# loadSwitchBreakoutBoard.net
KiCad netlist of a schematic drawn in EAGLE
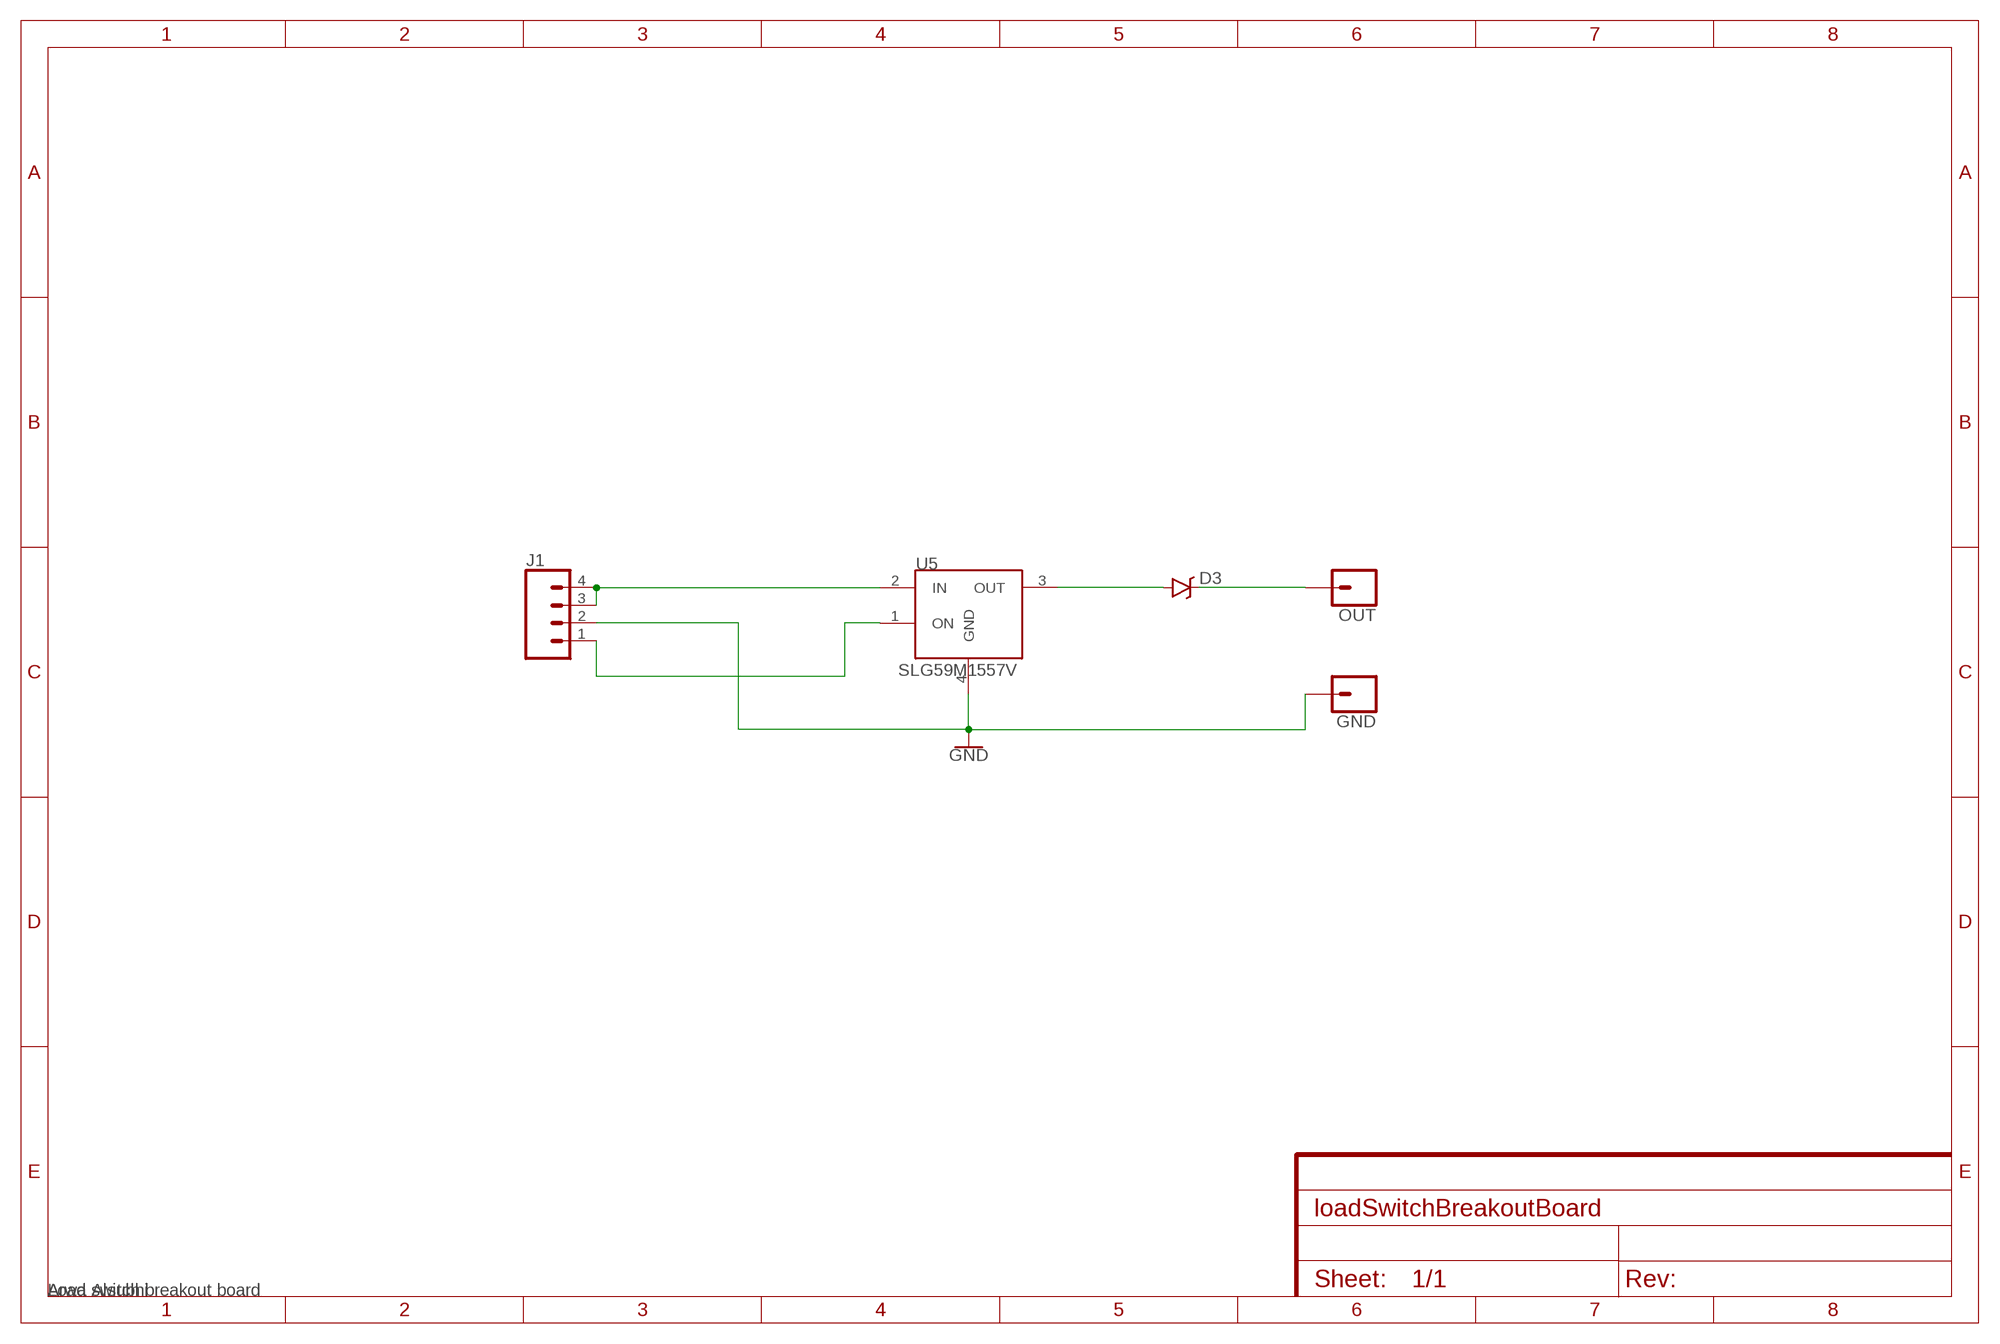
[diagram p0: schematic, sheet 1]

(export (version "E")
  (design (tool "Eeschema 10.0.6"))
  (components
    (comp (ref "D3")
      (value "RB751")
      (footprint "eagle-import:SOD-523")
      (fields (field (name "MPN") "BAS40-02V-V-G-08"))
      (libsource (lib "eagle-import") (part "DIODE-SCHOTTKY-RB751"))
    )
    (comp (ref "GND")
      (value "CONN_01")
      (footprint "eagle-import:1X01")
      (libsource (lib "eagle-import") (part "CONN_01"))
    )
    (comp (ref "J1")
      (value "CONN_04")
      (footprint "eagle-import:1X04")
      (libsource (lib "eagle-import") (part "CONN_04"))
    )
    (comp (ref "OUT")
      (value "CONN_01")
      (footprint "eagle-import:1X01")
      (libsource (lib "eagle-import") (part "CONN_01"))
    )
    (comp (ref "U5")
      (value "SLG59M1557V")
      (footprint "eagle-import:4STDFN")
      (fields (field (name "MPN") "SLG59M1557V "))
      (libsource (lib "eagle-import") (part "SLG59M1557V"))
    )
  )
  (nets
    (net (code "1") (name "GND") (class "Default")
      (node (ref "GND") (pin "1") (pinfunction "1_1") (pintype "passive"))
      (node (ref "J1") (pin "2") (pinfunction "2_2") (pintype "passive"))
      (node (ref "U5") (pin "4") (pinfunction "GND_4") (pintype "bidirectional"))
    )
    (net (code "2") (name "Net-(D3-PadC)") (class "Default")
      (node (ref "D3") (pin "C") (pinfunction "C_C") (pintype "passive"))
      (node (ref "OUT") (pin "1") (pinfunction "1_1") (pintype "passive"))
    )
    (net (code "3") (name "Net-(U5-IN)") (class "Default")
      (node (ref "J1") (pin "3") (pinfunction "3_3") (pintype "passive"))
      (node (ref "J1") (pin "4") (pinfunction "4_4") (pintype "passive"))
      (node (ref "U5") (pin "2") (pinfunction "IN_2") (pintype "bidirectional"))
    )
    (net (code "4") (name "Net-(U5-ON)") (class "Default")
      (node (ref "J1") (pin "1") (pinfunction "1_1") (pintype "passive"))
      (node (ref "U5") (pin "1") (pinfunction "ON_1") (pintype "bidirectional"))
    )
    (net (code "5") (name "Net-(U5-OUT)") (class "Default")
      (node (ref "D3") (pin "A") (pinfunction "A_A") (pintype "passive"))
      (node (ref "U5") (pin "3") (pinfunction "OUT_3") (pintype "bidirectional"))
    )
  )
)
